# 1_-power_sypply.net
KiCad netlist of a schematic drawn in Altium Designer
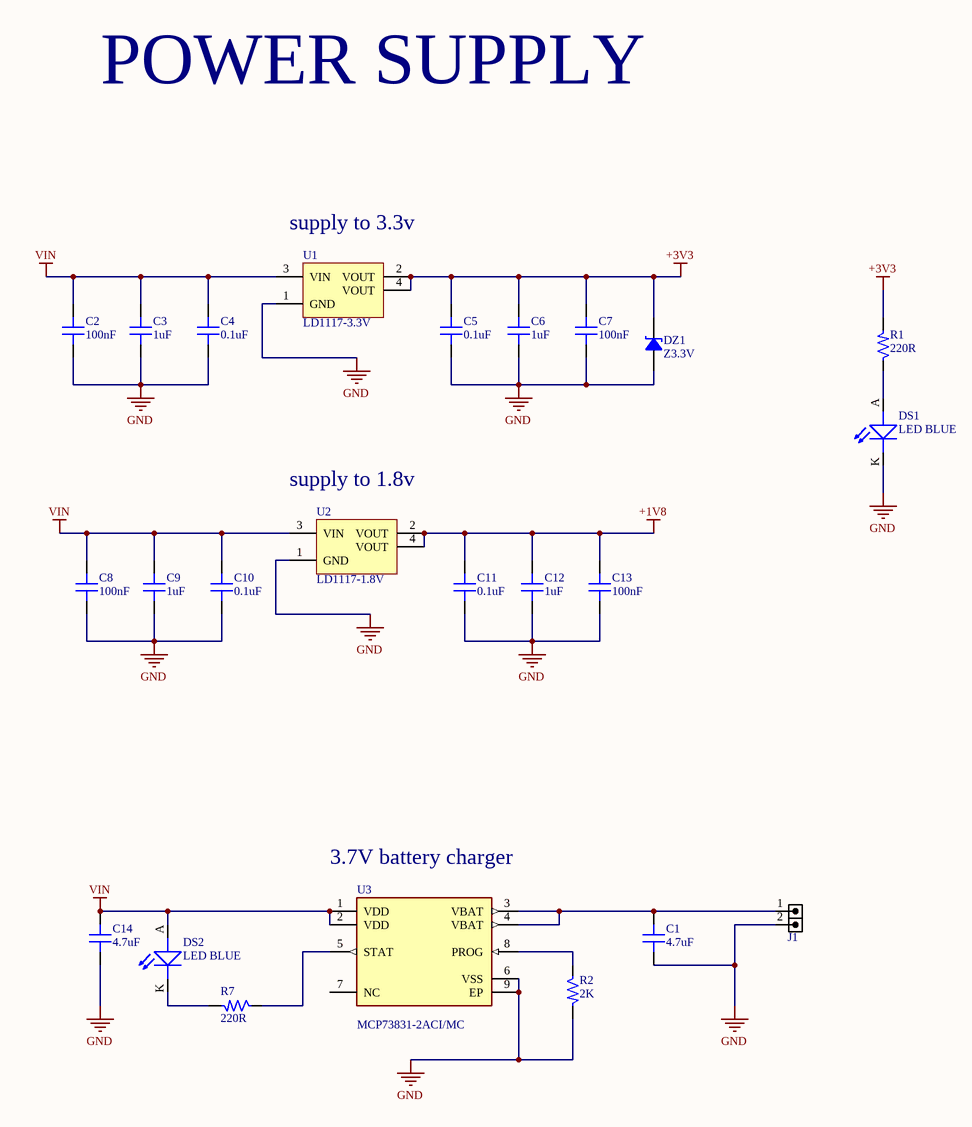
[diagram p0: [1]-power sypply.SchDoc]

(export (version "E")
  (design (tool "Eeschema 10.0.6"))
  (components
    (comp (ref "C1")
      (value "4.7uF")
      (footprint "CAP 0603_1608")
      (description "SMT Capacitor")
      (libsource (lib "Capacitor") (part "Cap 0603"))
    )
    (comp (ref "C2")
      (value "100nF")
      (footprint "CAP 0603_1608")
      (description "SMT Capacitor")
      (libsource (lib "Capacitor") (part "Cap 0603"))
    )
    (comp (ref "C3")
      (value "1uF")
      (footprint "CAP 0603_1608")
      (description "SMT Capacitor")
      (libsource (lib "Capacitor") (part "Cap 0603"))
    )
    (comp (ref "C4")
      (value "0.1uF")
      (footprint "CAP 0603_1608")
      (description "SMT Capacitor")
      (libsource (lib "Capacitor") (part "Cap 0603"))
    )
    (comp (ref "C5")
      (value "0.1uF")
      (footprint "CAP 0603_1608")
      (description "SMT Capacitor")
      (libsource (lib "Capacitor") (part "Cap 0603"))
    )
    (comp (ref "C6")
      (value "1uF")
      (footprint "CAP 0603_1608")
      (description "SMT Capacitor")
      (libsource (lib "Capacitor") (part "Cap 0603"))
    )
    (comp (ref "C7")
      (value "100nF")
      (footprint "CAP 0603_1608")
      (description "SMT Capacitor")
      (libsource (lib "Capacitor") (part "Cap 0603"))
    )
    (comp (ref "C8")
      (value "100nF")
      (footprint "CAP 0603_1608")
      (description "SMT Capacitor")
      (libsource (lib "Capacitor") (part "Cap 0603"))
    )
    (comp (ref "C9")
      (value "1uF")
      (footprint "CAP 0603_1608")
      (description "SMT Capacitor")
      (libsource (lib "Capacitor") (part "Cap 0603"))
    )
    (comp (ref "C10")
      (value "0.1uF")
      (footprint "CAP 0603_1608")
      (description "SMT Capacitor")
      (libsource (lib "Capacitor") (part "Cap 0603"))
    )
    (comp (ref "C11")
      (value "0.1uF")
      (footprint "CAP 0603_1608")
      (description "SMT Capacitor")
      (libsource (lib "Capacitor") (part "Cap 0603"))
    )
    (comp (ref "C12")
      (value "1uF")
      (footprint "CAP 0603_1608")
      (description "SMT Capacitor")
      (libsource (lib "Capacitor") (part "Cap 0603"))
    )
    (comp (ref "C13")
      (value "100nF")
      (footprint "CAP 0603_1608")
      (description "SMT Capacitor")
      (libsource (lib "Capacitor") (part "Cap 0603"))
    )
    (comp (ref "C14")
      (value "4.7uF")
      (footprint "CAP 0603_1608")
      (description "SMT Capacitor")
      (libsource (lib "Capacitor") (part "Cap 0603"))
    )
    (comp (ref "DS1")
      (value "LED BLUE")
      (footprint "LED_0805")
      (description "Blue 470nm LED Indication - Discrete 3.3V 0805 (2012 Metric)")
      (fields
        (field (name "MANUFACTURER") "Vishay Lite-On")
        (field (name "MANUFACTURER PART NUMBER") "LTST-C171TBKT")
      )
      (libsource (lib "ESTEEMPCBLIB") (part "LED_BLUE-3V3-20mA-0805"))
    )
    (comp (ref "DS2")
      (value "LED BLUE")
      (footprint "LED_0805")
      (description "Blue 470nm LED Indication - Discrete 3.3V 0805 (2012 Metric)")
      (fields
        (field (name "MANUFACTURER") "Vishay Lite-On")
        (field (name "MANUFACTURER PART NUMBER") "LTST-C171TBKT")
      )
      (libsource (lib "ESTEEMPCBLIB") (part "LED_BLUE-3V3-20mA-0805"))
    )
    (comp (ref "DZ1")
      (value "Z3.3V")
      (footprint "SOD-323")
      (description "Zener Diode")
      (fields (field (name "PARTNUMBER") "BZX384B3V3-G"))
      (libsource (lib "Diode") (part "Zener 200mW 3.3V (SMD SOD-323)"))
    )
    (comp (ref "J1")
      (value "HDR2")
      (footprint "HDR1SE_M_1X2")
      (description "HEADER, 1mm pitch, test, SMD")
      (libsource (lib "Conn Header") (part "HDRTST_1X2"))
    )
    (comp (ref "R1")
      (value "220R")
      (footprint "RES_0805")
      (description "220 Ohms ±1% 0.125W, 1/8W Chip Resistor 0805 (2012 Metric) Automotive AEC-Q200 Thick Film")
      (fields (field (name "MANUFACTURER") "Walsin") (field (name "MANUFACTURER PART NUMBER") "WR08X2200FTL"))
      (libsource (lib "ESTEEMPCBLIB") (part "RES_220R-0.125W-1%-0805"))
    )
    (comp (ref "R2")
      (value "2K")
      (footprint "RES_0805")
      (description "220 Ohms ±1% 0.125W, 1/8W Chip Resistor 0805 (2012 Metric) Automotive AEC-Q200 Thick Film")
      (fields (field (name "MANUFACTURER") "Walsin") (field (name "MANUFACTURER PART NUMBER") "WR08X2200FTL"))
      (libsource (lib "ESTEEMPCBLIB") (part "RES_220R-0.125W-1%-0805"))
    )
    (comp (ref "R7")
      (value "220R")
      (footprint "RES_0805")
      (description "220 Ohms ±1% 0.125W, 1/8W Chip Resistor 0805 (2012 Metric) Automotive AEC-Q200 Thick Film")
      (fields (field (name "MANUFACTURER") "Walsin") (field (name "MANUFACTURER PART NUMBER") "WR08X2200FTL"))
      (libsource (lib "ESTEEMPCBLIB") (part "RES_220R-0.125W-1%-0805"))
    )
    (comp (ref "U1")
      (value "LD1117-3.3V")
      (footprint "SOT-223-4 6.5X7MM P2.3MM")
      (description "Linear Voltage Regulator IC  1 Output  800mA SOT-223")
      (fields (field (name "PARTNUMBER") "LD1117S33CTR"))
      (libsource (lib "Chip") (part "LD1117-3.3V (SMD SOT-223)"))
    )
    (comp (ref "U2")
      (value "LD1117-1.8V")
      (footprint "SOT-223-4 6.5X7MM P2.3MM")
      (description "Linear Voltage Regulator IC  1 Output  800mA SOT-223")
      (fields (field (name "PARTNUMBER") "LD1117S18CTR"))
      (libsource (lib "Chip") (part "LD1117-1.8V (SMD SOT-223)"))
    )
    (comp (ref "U3")
      (value "MCP73831-2ACI/MC")
      (footprint "FP-C04-123-MFG")
      (description "IC CONTROLLER LI-ION 4.2V 8DFN")
      (fields
        (field (name "OCTOPART") "https://octopart.com/mcp73831-2aci%2Fmc-microchip-16517355")
        (field (name "MANUFACTURER") "Microchip")
      )
      (libsource (lib "Altium Content Vault") (part "ff4aef3c73132f256b0e29225c28959"))
    )
  )
  (nets
    (net (code "1") (name "+1V8") (class "Default")
      (node (ref "C11") (pin "2") (pinfunction "2_2") (pintype "passive"))
      (node (ref "C12") (pin "2") (pinfunction "2_2") (pintype "passive"))
      (node (ref "C13") (pin "2") (pinfunction "2_2") (pintype "passive"))
      (node (ref "U2") (pin "2") (pinfunction "VOUT_2") (pintype "passive"))
      (node (ref "U2") (pin "4") (pinfunction "VOUT_4") (pintype "passive"))
    )
    (net (code "2") (name "+3V3") (class "Default")
      (node (ref "C5") (pin "2") (pinfunction "2_2") (pintype "passive"))
      (node (ref "C6") (pin "2") (pinfunction "2_2") (pintype "passive"))
      (node (ref "C7") (pin "2") (pinfunction "2_2") (pintype "passive"))
      (node (ref "DZ1") (pin "2") (pinfunction "2_2") (pintype "passive"))
      (node (ref "R1") (pin "2") (pinfunction "2_2") (pintype "passive"))
      (node (ref "U1") (pin "2") (pinfunction "VOUT_2") (pintype "passive"))
      (node (ref "U1") (pin "4") (pinfunction "VOUT_4") (pintype "passive"))
    )
    (net (code "3") (name "GND") (class "Default")
      (node (ref "C1") (pin "1") (pinfunction "1_1") (pintype "passive"))
      (node (ref "C10") (pin "1") (pinfunction "1_1") (pintype "passive"))
      (node (ref "C11") (pin "1") (pinfunction "1_1") (pintype "passive"))
      (node (ref "C12") (pin "1") (pinfunction "1_1") (pintype "passive"))
      (node (ref "C13") (pin "1") (pinfunction "1_1") (pintype "passive"))
      (node (ref "C14") (pin "1") (pinfunction "1_1") (pintype "passive"))
      (node (ref "C2") (pin "1") (pinfunction "1_1") (pintype "passive"))
      (node (ref "C3") (pin "1") (pinfunction "1_1") (pintype "passive"))
      (node (ref "C4") (pin "1") (pinfunction "1_1") (pintype "passive"))
      (node (ref "C5") (pin "1") (pinfunction "1_1") (pintype "passive"))
      (node (ref "C6") (pin "1") (pinfunction "1_1") (pintype "passive"))
      (node (ref "C7") (pin "1") (pinfunction "1_1") (pintype "passive"))
      (node (ref "C8") (pin "1") (pinfunction "1_1") (pintype "passive"))
      (node (ref "C9") (pin "1") (pinfunction "1_1") (pintype "passive"))
      (node (ref "DS1") (pin "K") (pinfunction "CATHODE_K") (pintype "passive"))
      (node (ref "DZ1") (pin "1") (pinfunction "1_1") (pintype "passive"))
      (node (ref "J1") (pin "2") (pinfunction "2_2") (pintype "passive"))
      (node (ref "R2") (pin "2") (pinfunction "2_2") (pintype "passive"))
      (node (ref "U1") (pin "1") (pinfunction "GND_1") (pintype "passive"))
      (node (ref "U2") (pin "1") (pinfunction "GND_1") (pintype "passive"))
      (node (ref "U3") (pin "6") (pinfunction "VSS_6") (pintype "power_in"))
      (node (ref "U3") (pin "9") (pinfunction "EP_9") (pintype "power_in"))
    )
    (net (code "4") (name "Net-(C1-Pad2)") (class "Default")
      (node (ref "C1") (pin "2") (pinfunction "2_2") (pintype "passive"))
      (node (ref "J1") (pin "1") (pinfunction "1_1") (pintype "passive"))
      (node (ref "U3") (pin "3") (pinfunction "VBAT_3") (pintype "output"))
      (node (ref "U3") (pin "4") (pinfunction "VBAT_4") (pintype "output"))
    )
    (net (code "5") (name "Net-(DS1-ANODE)") (class "Default")
      (node (ref "DS1") (pin "A") (pinfunction "ANODE_A") (pintype "passive"))
      (node (ref "R1") (pin "1") (pinfunction "1_1") (pintype "passive"))
    )
    (net (code "6") (name "Net-(DS2-CATHODE)") (class "Default")
      (node (ref "DS2") (pin "K") (pinfunction "CATHODE_K") (pintype "passive"))
      (node (ref "R7") (pin "2") (pinfunction "2_2") (pintype "passive"))
    )
    (net (code "7") (name "Net-(U3-PROG)") (class "Default")
      (node (ref "R2") (pin "1") (pinfunction "1_1") (pintype "passive"))
      (node (ref "U3") (pin "8") (pinfunction "PROG_8") (pintype "input"))
    )
    (net (code "8") (name "Net-(U3-STAT)") (class "Default")
      (node (ref "R7") (pin "1") (pinfunction "1_1") (pintype "passive"))
      (node (ref "U3") (pin "5") (pinfunction "STAT_5") (pintype "output"))
    )
    (net (code "9") (name "VIN") (class "Default")
      (node (ref "C10") (pin "2") (pinfunction "2_2") (pintype "passive"))
      (node (ref "C14") (pin "2") (pinfunction "2_2") (pintype "passive"))
      (node (ref "C2") (pin "2") (pinfunction "2_2") (pintype "passive"))
      (node (ref "C3") (pin "2") (pinfunction "2_2") (pintype "passive"))
      (node (ref "C4") (pin "2") (pinfunction "2_2") (pintype "passive"))
      (node (ref "C8") (pin "2") (pinfunction "2_2") (pintype "passive"))
      (node (ref "C9") (pin "2") (pinfunction "2_2") (pintype "passive"))
      (node (ref "DS2") (pin "A") (pinfunction "ANODE_A") (pintype "passive"))
      (node (ref "U1") (pin "3") (pinfunction "VIN_3") (pintype "passive"))
      (node (ref "U2") (pin "3") (pinfunction "VIN_3") (pintype "passive"))
      (node (ref "U3") (pin "1") (pinfunction "VDD_1") (pintype "power_in"))
      (node (ref "U3") (pin "2") (pinfunction "VDD_2") (pintype "power_in"))
    )
    (net (code "10") (name "unconnected-(U3-NC-Pad7)") (class "Default")
      (node (ref "U3") (pin "7") (pinfunction "NC_7") (pintype "passive"))
    )
  )
)
